# schematic.net
KiCad netlist of a schematic drawn in EasyEDA
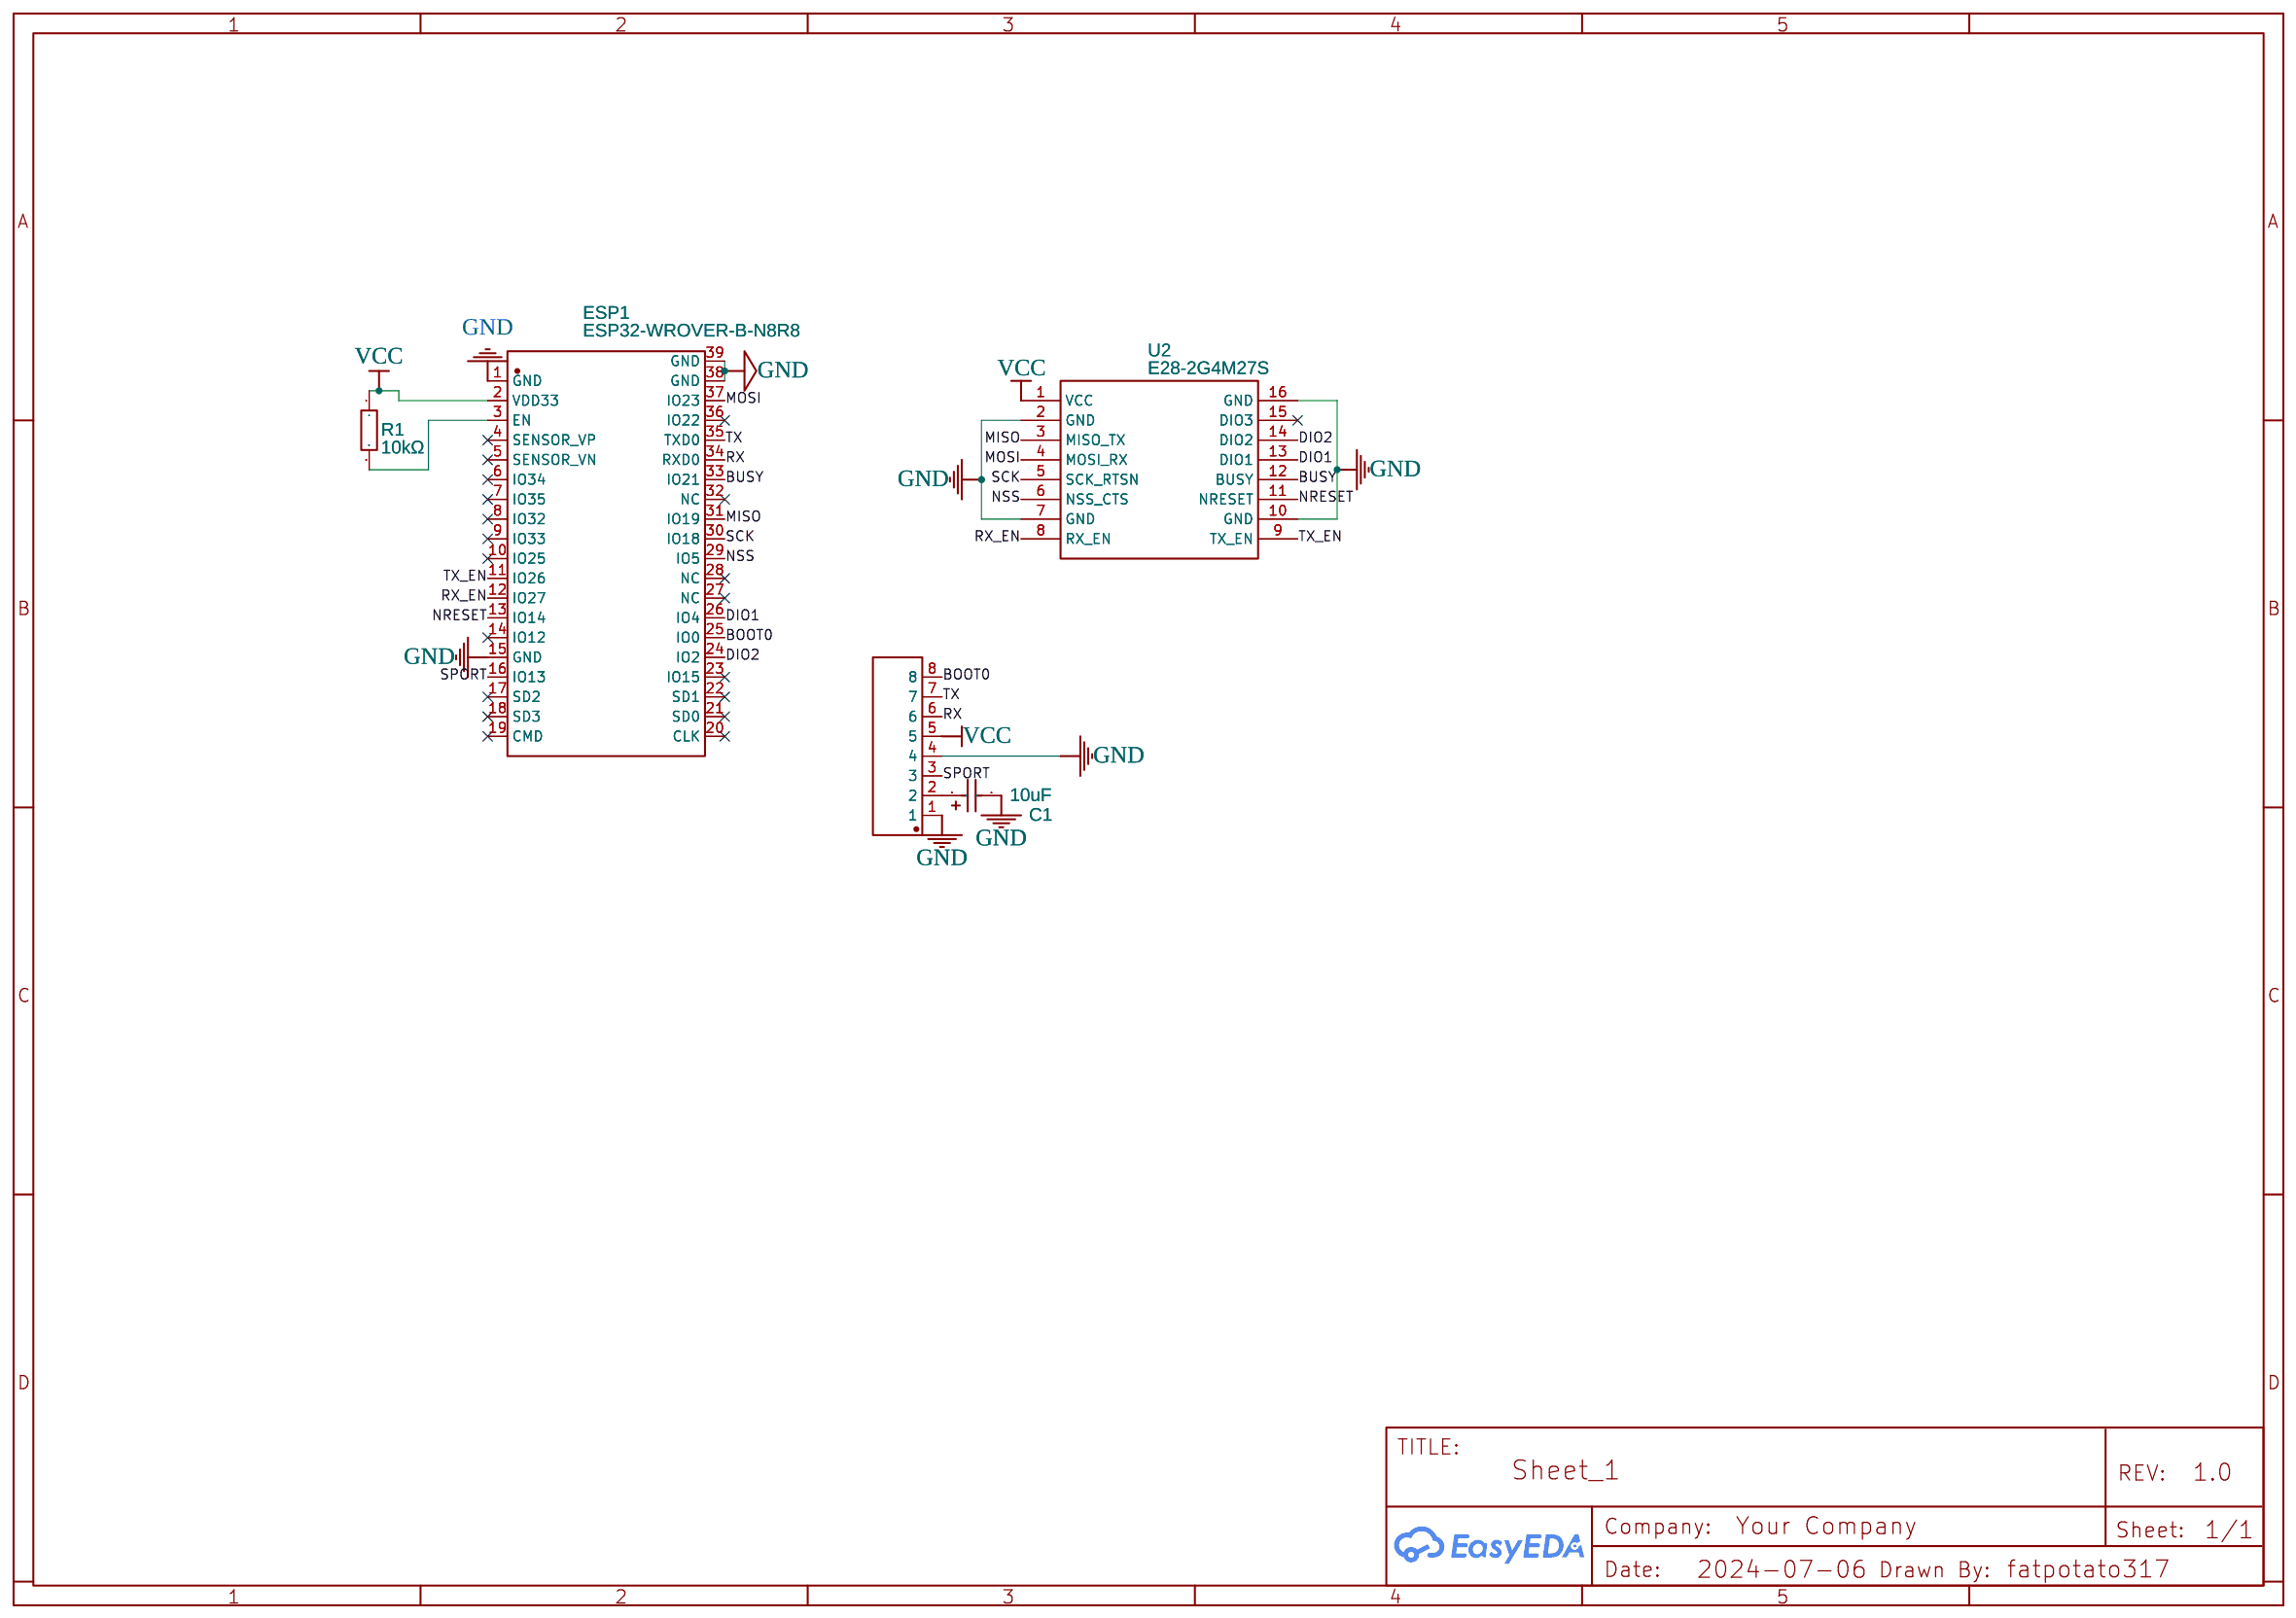
[diagram p0: schematic sheet]

(export (version "E")
  (design (tool "Eeschema 10.0.6"))
  (components
    (comp (ref "C1")
      (value "10uF")
      (fields (field (name "Manufacturer Part") "TAJA106K016RNJ") (field (name "Manufacturer") "Kyocera AVX"))
      (libsource (lib "") (part "TAJA106K016RNJ"))
    )
    (comp (ref "ESP1")
      (value "ESP32-WROVER-B-N8R8")
      (fields (field (name "Manufacturer") "ESPRESSIF(乐鑫)"))
      (libsource (lib "") (part "ESP32-WROVER-B-N8R8"))
    )
    (comp (ref "H1")
      (value "1.27mm1*8P Straight Headers  Pins")
      (fields (field (name "Manufacturer Part") "1.27mm1*10P 直 排针"))
      (libsource (lib "") (part "1.27mm1*8P Straight Headers  Pins"))
    )
    (comp (ref "R1")
      (value "10kΩ")
      (fields
        (field (name "Manufacturer Part") "0603WAF1002T5E")
        (field (name "Manufacturer") "UNI-ROYAL(厚声)")
      )
      (libsource (lib "") (part "0603WAF1002T5E"))
    )
    (comp (ref "U2")
      (value "E28-2G4M27S")
      (fields (field (name "Manufacturer") "EBYTE(亿佰特)"))
      (libsource (lib "") (part "E28-2G4M27S"))
    )
  )
  (nets
    (net (code "1") (name "/BOOT0") (class "Default")
      (node (ref "ESP1") (pin "25") (pinfunction "IO0_25") (pintype "unspecified"))
      (node (ref "H1") (pin "8") (pinfunction "8_8") (pintype "unspecified"))
    )
    (net (code "2") (name "/BUSY") (class "Default")
      (node (ref "ESP1") (pin "33") (pinfunction "IO21_33") (pintype "unspecified"))
      (node (ref "U2") (pin "12") (pinfunction "BUSY_12") (pintype "unspecified"))
    )
    (net (code "3") (name "/DIO1") (class "Default")
      (node (ref "ESP1") (pin "26") (pinfunction "IO4_26") (pintype "unspecified"))
      (node (ref "U2") (pin "13") (pinfunction "DIO1_13") (pintype "unspecified"))
    )
    (net (code "4") (name "/DIO2") (class "Default")
      (node (ref "ESP1") (pin "24") (pinfunction "IO2_24") (pintype "unspecified"))
      (node (ref "U2") (pin "14") (pinfunction "DIO2_14") (pintype "unspecified"))
    )
    (net (code "5") (name "/MISO") (class "Default")
      (node (ref "ESP1") (pin "31") (pinfunction "IO19_31") (pintype "unspecified"))
      (node (ref "U2") (pin "3") (pinfunction "MISO_TX_3") (pintype "unspecified"))
    )
    (net (code "6") (name "/MOSI") (class "Default")
      (node (ref "ESP1") (pin "37") (pinfunction "IO23_37") (pintype "unspecified"))
      (node (ref "U2") (pin "4") (pinfunction "MOSI_RX_4") (pintype "unspecified"))
    )
    (net (code "7") (name "/NRESET") (class "Default")
      (node (ref "ESP1") (pin "13") (pinfunction "IO14_13") (pintype "unspecified"))
      (node (ref "U2") (pin "11") (pinfunction "NRESET_11") (pintype "unspecified"))
    )
    (net (code "8") (name "/NSS") (class "Default")
      (node (ref "ESP1") (pin "29") (pinfunction "IO5_29") (pintype "unspecified"))
      (node (ref "U2") (pin "6") (pinfunction "NSS_CTS_6") (pintype "unspecified"))
    )
    (net (code "9") (name "/RX") (class "Default")
      (node (ref "ESP1") (pin "34") (pinfunction "RXD0_34") (pintype "unspecified"))
      (node (ref "H1") (pin "6") (pinfunction "6_6") (pintype "unspecified"))
    )
    (net (code "10") (name "/RX_EN") (class "Default")
      (node (ref "ESP1") (pin "12") (pinfunction "IO27_12") (pintype "unspecified"))
      (node (ref "U2") (pin "8") (pinfunction "RX_EN_8") (pintype "unspecified"))
    )
    (net (code "11") (name "/SCK") (class "Default")
      (node (ref "ESP1") (pin "30") (pinfunction "IO18_30") (pintype "unspecified"))
      (node (ref "U2") (pin "5") (pinfunction "SCK_RTSN_5") (pintype "unspecified"))
    )
    (net (code "12") (name "/SPORT") (class "Default")
      (node (ref "ESP1") (pin "16") (pinfunction "IO13_16") (pintype "unspecified"))
      (node (ref "H1") (pin "3") (pinfunction "3_3") (pintype "unspecified"))
    )
    (net (code "13") (name "/TX") (class "Default")
      (node (ref "ESP1") (pin "35") (pinfunction "TXD0_35") (pintype "unspecified"))
      (node (ref "H1") (pin "7") (pinfunction "7_7") (pintype "unspecified"))
    )
    (net (code "14") (name "/TX_EN") (class "Default")
      (node (ref "ESP1") (pin "11") (pinfunction "IO26_11") (pintype "unspecified"))
      (node (ref "U2") (pin "9") (pinfunction "TX_EN_9") (pintype "unspecified"))
    )
    (net (code "15") (name "GND") (class "Default")
      (node (ref "C1") (pin "2") (pinfunction "2_2") (pintype "unspecified"))
      (node (ref "ESP1") (pin "1") (pinfunction "GND_1") (pintype "unspecified"))
      (node (ref "ESP1") (pin "15") (pinfunction "GND_15") (pintype "unspecified"))
      (node (ref "ESP1") (pin "38") (pinfunction "GND_38") (pintype "unspecified"))
      (node (ref "ESP1") (pin "39") (pinfunction "GND_39") (pintype "unspecified"))
      (node (ref "H1") (pin "1") (pinfunction "1_1") (pintype "unspecified"))
      (node (ref "H1") (pin "4") (pinfunction "4_4") (pintype "unspecified"))
      (node (ref "U2") (pin "10") (pinfunction "GND_10") (pintype "unspecified"))
      (node (ref "U2") (pin "16") (pinfunction "GND_16") (pintype "unspecified"))
      (node (ref "U2") (pin "2") (pinfunction "GND_2") (pintype "unspecified"))
      (node (ref "U2") (pin "7") (pinfunction "GND_7") (pintype "unspecified"))
    )
    (net (code "16") (name "Net-(C1-Pad1)") (class "Default")
      (node (ref "C1") (pin "1") (pinfunction "1_1") (pintype "unspecified"))
      (node (ref "H1") (pin "2") (pinfunction "2_2") (pintype "unspecified"))
    )
    (net (code "17") (name "Net-(ESP1-EN)") (class "Default")
      (node (ref "ESP1") (pin "3") (pinfunction "EN_3") (pintype "unspecified"))
      (node (ref "R1") (pin "2") (pinfunction "2_2") (pintype "input"))
    )
    (net (code "18") (name "VCC") (class "Default")
      (node (ref "ESP1") (pin "2") (pinfunction "VDD33_2") (pintype "unspecified"))
      (node (ref "H1") (pin "5") (pinfunction "5_5") (pintype "unspecified"))
      (node (ref "R1") (pin "1") (pinfunction "1_1") (pintype "input"))
      (node (ref "U2") (pin "1") (pinfunction "VCC_1") (pintype "unspecified"))
    )
    (net (code "19") (name "unconnected-(ESP1-CLK-Pad20)") (class "Default")
      (node (ref "ESP1") (pin "20") (pinfunction "CLK_20") (pintype "unspecified+no_connect"))
    )
    (net (code "20") (name "unconnected-(ESP1-CMD-Pad19)") (class "Default")
      (node (ref "ESP1") (pin "19") (pinfunction "CMD_19") (pintype "unspecified+no_connect"))
    )
    (net (code "21") (name "unconnected-(ESP1-IO12-Pad14)") (class "Default")
      (node (ref "ESP1") (pin "14") (pinfunction "IO12_14") (pintype "unspecified+no_connect"))
    )
    (net (code "22") (name "unconnected-(ESP1-IO15-Pad23)") (class "Default")
      (node (ref "ESP1") (pin "23") (pinfunction "IO15_23") (pintype "unspecified+no_connect"))
    )
    (net (code "23") (name "unconnected-(ESP1-IO22-Pad36)") (class "Default")
      (node (ref "ESP1") (pin "36") (pinfunction "IO22_36") (pintype "unspecified+no_connect"))
    )
    (net (code "24") (name "unconnected-(ESP1-IO25-Pad10)") (class "Default")
      (node (ref "ESP1") (pin "10") (pinfunction "IO25_10") (pintype "unspecified+no_connect"))
    )
    (net (code "25") (name "unconnected-(ESP1-IO32-Pad8)") (class "Default")
      (node (ref "ESP1") (pin "8") (pinfunction "IO32_8") (pintype "unspecified+no_connect"))
    )
    (net (code "26") (name "unconnected-(ESP1-IO33-Pad9)") (class "Default")
      (node (ref "ESP1") (pin "9") (pinfunction "IO33_9") (pintype "unspecified+no_connect"))
    )
    (net (code "27") (name "unconnected-(ESP1-IO34-Pad6)") (class "Default")
      (node (ref "ESP1") (pin "6") (pinfunction "IO34_6") (pintype "unspecified+no_connect"))
    )
    (net (code "28") (name "unconnected-(ESP1-IO35-Pad7)") (class "Default")
      (node (ref "ESP1") (pin "7") (pinfunction "IO35_7") (pintype "unspecified+no_connect"))
    )
    (net (code "29") (name "unconnected-(ESP1-NC-Pad27)") (class "Default")
      (node (ref "ESP1") (pin "27") (pinfunction "NC_27") (pintype "unspecified+no_connect"))
    )
    (net (code "30") (name "unconnected-(ESP1-NC-Pad28)") (class "Default")
      (node (ref "ESP1") (pin "28") (pinfunction "NC_28") (pintype "unspecified+no_connect"))
    )
    (net (code "31") (name "unconnected-(ESP1-NC-Pad32)") (class "Default")
      (node (ref "ESP1") (pin "32") (pinfunction "NC_32") (pintype "unspecified+no_connect"))
    )
    (net (code "32") (name "unconnected-(ESP1-SD0-Pad21)") (class "Default")
      (node (ref "ESP1") (pin "21") (pinfunction "SD0_21") (pintype "unspecified+no_connect"))
    )
    (net (code "33") (name "unconnected-(ESP1-SD1-Pad22)") (class "Default")
      (node (ref "ESP1") (pin "22") (pinfunction "SD1_22") (pintype "unspecified+no_connect"))
    )
    (net (code "34") (name "unconnected-(ESP1-SD2-Pad17)") (class "Default")
      (node (ref "ESP1") (pin "17") (pinfunction "SD2_17") (pintype "unspecified+no_connect"))
    )
    (net (code "35") (name "unconnected-(ESP1-SD3-Pad18)") (class "Default")
      (node (ref "ESP1") (pin "18") (pinfunction "SD3_18") (pintype "unspecified+no_connect"))
    )
    (net (code "36") (name "unconnected-(ESP1-SENSOR_VN-Pad5)") (class "Default")
      (node (ref "ESP1") (pin "5") (pinfunction "SENSOR_VN_5") (pintype "unspecified+no_connect"))
    )
    (net (code "37") (name "unconnected-(ESP1-SENSOR_VP-Pad4)") (class "Default")
      (node (ref "ESP1") (pin "4") (pinfunction "SENSOR_VP_4") (pintype "unspecified+no_connect"))
    )
    (net (code "38") (name "unconnected-(U2-DIO3-Pad15)") (class "Default")
      (node (ref "U2") (pin "15") (pinfunction "DIO3_15") (pintype "unspecified+no_connect"))
    )
  )
)
